# diapers.net
KiCad netlist of a schematic drawn in Altium Designer
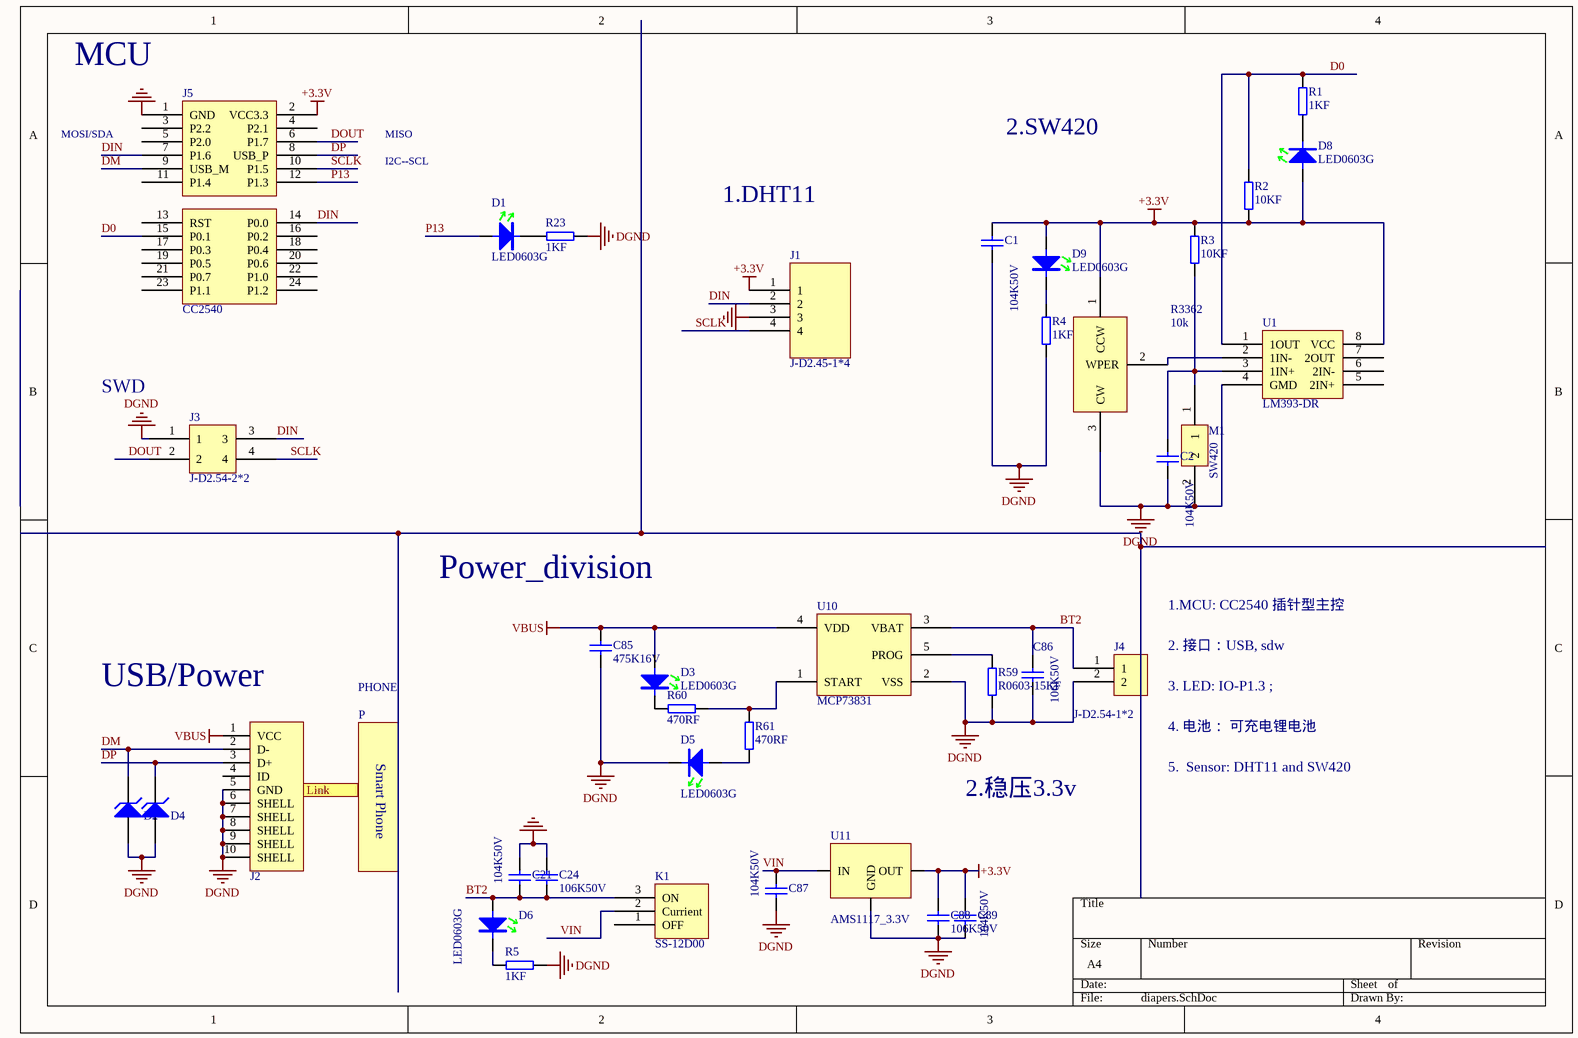
[diagram p0: diapers.SchDoc]

(export (version "E")
  (design (tool "Eeschema 10.0.6"))
  (components
    (comp (ref "C1")
      (value "104K50V")
      (footprint "C0603")
      (description "贴片电容-陶瓷")
      (libsource (lib "Capacitor") (part "C0603X7R-104K50V"))
    )
    (comp (ref "C2")
      (value "104K50V")
      (footprint "C0603")
      (description "贴片电容-陶瓷")
      (libsource (lib "Capacitor") (part "C0603X7R-104K50V"))
    )
    (comp (ref "C21")
      (value "104K50V")
      (footprint "C0603")
      (description "贴片电容-陶瓷")
      (libsource (lib "Capacitor") (part "C0603X7R-104K50V"))
    )
    (comp (ref "C24")
      (value "106K50V")
      (footprint "C0603")
      (description "贴片电容-陶瓷")
      (libsource (lib "Capacitor") (part "C0603X7R-106K50V"))
    )
    (comp (ref "C85")
      (value "475K16V")
      (footprint "C0603")
      (description "贴片电容-陶瓷")
      (libsource (lib "Capacitor") (part "C0603X7R-475K16V"))
    )
    (comp (ref "C86")
      (value "106K50V")
      (footprint "C0603")
      (description "贴片电容-陶瓷")
      (libsource (lib "Capacitor") (part "C0603X7R-106K50V"))
    )
    (comp (ref "C87")
      (value "104K50V")
      (footprint "C0603")
      (description "贴片电容-陶瓷")
      (libsource (lib "Capacitor") (part "C0603X7R-104K50V"))
    )
    (comp (ref "C88")
      (value "106K50V")
      (footprint "C0603")
      (description "贴片电容-陶瓷")
      (libsource (lib "Capacitor") (part "C0603X7R-106K50V"))
    )
    (comp (ref "C89")
      (value "104K50V")
      (footprint "C0603")
      (description "贴片电容-陶瓷")
      (libsource (lib "Capacitor") (part "C0603X7R-104K50V"))
    )
    (comp (ref "D1")
      (value "LED0603G")
      (footprint "D-LED0603G")
      (description "贴片二极管-LED")
      (libsource (lib "aiwacV2.0") (part "DLED-0603-G"))
    )
    (comp (ref "D2")
      (value "ESDA_TR1/0603")
      (footprint "HS_0603D")
      (description "Zener Diode")
      (fields (field (name "PUBLISHER") "*"))
      (libsource (lib "aiwacV2.0") (part "D Zener"))
    )
    (comp (ref "D3")
      (value "LED0603G")
      (footprint "D-LED0603G")
      (description "贴片二极管-LED")
      (libsource (lib "Diode") (part "DLED-0603-G"))
    )
    (comp (ref "D4")
      (value "ESDA_TR1/0603")
      (footprint "HS_0603D")
      (description "Zener Diode")
      (fields (field (name "PUBLISHER") "*"))
      (libsource (lib "aiwacV2.0") (part "D Zener"))
    )
    (comp (ref "D5")
      (value "LED0603G")
      (footprint "D-LED0603G")
      (description "贴片二极管-LED")
      (libsource (lib "Diode") (part "DLED-0603-G"))
    )
    (comp (ref "D6")
      (value "LED0603G")
      (footprint "D-LED0603G")
      (description "贴片二极管-LED")
      (libsource (lib "aiwacV2.0") (part "DLED-0603-G"))
    )
    (comp (ref "D8")
      (value "LED0603G")
      (footprint "D-LED0603G")
      (description "贴片二极管-LED")
      (libsource (lib "Diode") (part "DLED-0603-G"))
    )
    (comp (ref "D9")
      (value "LED0603G")
      (footprint "D-LED0603G")
      (description "贴片二极管-LED")
      (libsource (lib "Diode") (part "DLED-0603-G"))
    )
    (comp (ref "J1")
      (value "J-D2.45-1*4")
      (footprint "D2.54-1*4P")
      (libsource (lib "Connector") (part "J-D2.54-1*4单排排母"))
    )
    (comp (ref "J2")
      (value "USB-MINI-SOCKET")
      (footprint "MICRO-USB - 5.9")
      (description "USB-A卧式插座")
      (libsource (lib "epic2") (part "J-USB-MINI-SOCKET"))
    )
    (comp (ref "J3")
      (value "J-D2.54-2*2")
      (footprint "D2.54-2*2P")
      (description "双排排针-直针")
      (libsource (lib "Connector") (part "J-D2.54-2*2双排"))
    )
    (comp (ref "J4")
      (value "J-D2.54-1*2")
      (footprint "D2.54-1*2P")
      (libsource (lib "Connector") (part "J-D2.54-1*2单排"))
    )
    (comp (ref "J5")
      (value "CC2540")
      (footprint "PCBComponent_1")
      (description "蓝牙主控模块的接口")
      (libsource (lib "Module") (part "CC2540"))
    )
    (comp (ref "K1")
      (value "SS-12D00")
      (footprint "SS-12D00")
      (libsource (lib "Key") (part "SS-12D00(1P2T) 立式 柄高5MM"))
    )
    (comp (ref "M1")
      (value "SW420")
      (footprint "SW420")
      (description "长闭震动开关")
      (libsource (lib "Module") (part "SW420"))
    )
    (comp (ref "P") (value "PHONE") (libsource (lib "epic") (part "PHONE")))
    (comp (ref "R1")
      (value "1KF")
      (footprint "R0603")
      (description "贴片电阻-通用")
      (libsource (lib "Resistor") (part "R0603-1KF"))
    )
    (comp (ref "R2")
      (value "10KF")
      (footprint "R0603")
      (description "贴片电阻-通用")
      (libsource (lib "Resistor") (part "R0603-10KF"))
    )
    (comp (ref "R3")
      (value "10KF")
      (footprint "R0603")
      (description "贴片电阻-通用")
      (libsource (lib "Resistor") (part "R0603-10KF"))
    )
    (comp (ref "R4")
      (value "1KF")
      (footprint "R0603")
      (description "贴片电阻-通用")
      (libsource (lib "Resistor") (part "R0603-1KF"))
    )
    (comp (ref "R5")
      (value "1KF")
      (footprint "R0603")
      (description "贴片电阻-通用")
      (libsource (lib "Resistor") (part "R0603-1KF"))
    )
    (comp (ref "R23")
      (value "1KF")
      (footprint "R0603")
      (description "贴片电阻-通用")
      (libsource (lib "Resistor") (part "R0603-1KF"))
    )
    (comp (ref "R59")
      (value "R0603-15KF")
      (footprint "R0603")
      (description "贴片电容-通用")
      (libsource (lib "Resistor") (part "R0603-15KF"))
    )
    (comp (ref "R60")
      (value "470RF")
      (footprint "R0603")
      (description "贴片电阻-通用")
      (libsource (lib "Resistor") (part "R0603-470RF"))
    )
    (comp (ref "R61")
      (value "470RF")
      (footprint "R0603")
      (description "贴片电阻-通用")
      (libsource (lib "Resistor") (part "R0603-470RF"))
    )
    (comp (ref "R3362")
      (value "10k")
      (footprint "R3326P")
      (description "电位器精密可调电阻")
      (libsource (lib "Resistor") (part "R3362-10K"))
    )
    (comp (ref "U1")
      (value "LM393-DR")
      (footprint "LM393")
      (description "双路比较器")
      (libsource (lib "IC") (part "LM393-DR"))
    )
    (comp (ref "U10")
      (value "MCP73831")
      (footprint "SOT23-5N")
      (description "charge IC")
      (libsource (lib "IC") (part "MCP73831"))
    )
    (comp (ref "U11")
      (value "AMS1117_3.3V")
      (footprint "SOT-223")
      (libsource (lib "IC") (part "AMS1117-3.3V"))
    )
  )
  (nets
    (net (code "1") (name "+3.3V") (class "Default")
      (node (ref "C1") (pin "1") (pinfunction "1_1") (pintype "passive"))
      (node (ref "C88") (pin "2") (pinfunction "2_2") (pintype "passive"))
      (node (ref "C89") (pin "1") (pinfunction "1_1") (pintype "passive"))
      (node (ref "D8") (pin "1") (pinfunction "1_1") (pintype "passive"))
      (node (ref "D9") (pin "1") (pinfunction "1_1") (pintype "passive"))
      (node (ref "J1") (pin "1") (pinfunction "1_1") (pintype "passive"))
      (node (ref "J5") (pin "2") (pinfunction "VCC3.3_2") (pintype "passive"))
      (node (ref "R2") (pin "1") (pinfunction "1_1") (pintype "passive"))
      (node (ref "R3") (pin "2") (pinfunction "2_2") (pintype "passive"))
      (node (ref "R3362") (pin "1") (pinfunction "CCW_1") (pintype "passive"))
      (node (ref "U1") (pin "8") (pinfunction "VCC_8") (pintype "passive"))
      (node (ref "U11") (pin "2") (pinfunction "OUT_2") (pintype "passive"))
    )
    (net (code "2") (name "/BT2") (class "Default")
      (node (ref "C21") (pin "2") (pinfunction "2_2") (pintype "passive"))
      (node (ref "C24") (pin "1") (pinfunction "1_1") (pintype "passive"))
      (node (ref "C86") (pin "1") (pinfunction "1_1") (pintype "passive"))
      (node (ref "D6") (pin "1") (pinfunction "1_1") (pintype "passive"))
      (node (ref "J4") (pin "1") (pinfunction "1_1") (pintype "passive"))
      (node (ref "K1") (pin "3") (pinfunction "ON_3") (pintype "passive"))
      (node (ref "U10") (pin "3") (pinfunction "VBAT_3") (pintype "passive"))
    )
    (net (code "3") (name "/D0") (class "Default")
      (node (ref "J5") (pin "15") (pinfunction "P0.1_15") (pintype "passive"))
      (node (ref "R1") (pin "1") (pinfunction "1_1") (pintype "passive"))
      (node (ref "R2") (pin "2") (pinfunction "2_2") (pintype "passive"))
      (node (ref "U1") (pin "1") (pinfunction "1OUT_1") (pintype "passive"))
    )
    (net (code "4") (name "/DIN") (class "Default")
      (node (ref "J1") (pin "2") (pinfunction "2_2") (pintype "passive"))
      (node (ref "J3") (pin "3") (pinfunction "3_3") (pintype "passive"))
      (node (ref "J5") (pin "14") (pinfunction "P0.0_14") (pintype "passive"))
      (node (ref "J5") (pin "7") (pinfunction "P1.6_7") (pintype "passive"))
    )
    (net (code "5") (name "/DM") (class "Default")
      (node (ref "D2") (pin "2") (pinfunction "K_2") (pintype "passive"))
      (node (ref "J2") (pin "2") (pinfunction "D-_2") (pintype "passive"))
      (node (ref "J5") (pin "9") (pinfunction "USB_M_9") (pintype "passive"))
    )
    (net (code "6") (name "/DOUT") (class "Default")
      (node (ref "J3") (pin "2") (pinfunction "2_2") (pintype "passive"))
      (node (ref "J5") (pin "6") (pinfunction "P1.7_6") (pintype "passive"))
    )
    (net (code "7") (name "/DP") (class "Default")
      (node (ref "D4") (pin "2") (pinfunction "K_2") (pintype "passive"))
      (node (ref "J2") (pin "3") (pinfunction "D+_3") (pintype "passive"))
      (node (ref "J5") (pin "8") (pinfunction "USB_P_8") (pintype "passive"))
    )
    (net (code "9") (name "/P13") (class "Default")
      (node (ref "D1") (pin "1") (pinfunction "1_1") (pintype "passive"))
      (node (ref "J5") (pin "12") (pinfunction "P1.3_12") (pintype "passive"))
    )
    (net (code "10") (name "/SCLK") (class "Default")
      (node (ref "J1") (pin "4") (pinfunction "4_4") (pintype "passive"))
      (node (ref "J3") (pin "4") (pinfunction "4_4") (pintype "passive"))
      (node (ref "J5") (pin "10") (pinfunction "P1.5_10") (pintype "passive"))
    )
    (net (code "11") (name "/VIN") (class "Default")
      (node (ref "C87") (pin "1") (pinfunction "1_1") (pintype "passive"))
      (node (ref "K1") (pin "2") (pinfunction "Currient_2") (pintype "passive"))
      (node (ref "U11") (pin "3") (pinfunction "IN_3") (pintype "passive"))
    )
    (net (code "12") (name "DGND") (class "Default")
      (node (ref "C1") (pin "2") (pinfunction "2_2") (pintype "passive"))
      (node (ref "C2") (pin "2") (pinfunction "2_2") (pintype "passive"))
      (node (ref "C21") (pin "1") (pinfunction "1_1") (pintype "passive"))
      (node (ref "C24") (pin "2") (pinfunction "2_2") (pintype "passive"))
      (node (ref "C85") (pin "2") (pinfunction "2_2") (pintype "passive"))
      (node (ref "C86") (pin "2") (pinfunction "2_2") (pintype "passive"))
      (node (ref "C87") (pin "2") (pinfunction "2_2") (pintype "passive"))
      (node (ref "C88") (pin "1") (pinfunction "1_1") (pintype "passive"))
      (node (ref "C89") (pin "2") (pinfunction "2_2") (pintype "passive"))
      (node (ref "D2") (pin "1") (pinfunction "A_1") (pintype "passive"))
      (node (ref "D4") (pin "1") (pinfunction "A_1") (pintype "passive"))
      (node (ref "D5") (pin "2") (pinfunction "2_2") (pintype "passive"))
      (node (ref "J1") (pin "3") (pinfunction "3_3") (pintype "passive"))
      (node (ref "J2") (pin "10") (pinfunction "SHELL_10") (pintype "passive"))
      (node (ref "J2") (pin "5") (pinfunction "GND_5") (pintype "passive"))
      (node (ref "J2") (pin "6") (pinfunction "SHELL_6") (pintype "passive"))
      (node (ref "J2") (pin "7") (pinfunction "SHELL_7") (pintype "passive"))
      (node (ref "J2") (pin "8") (pinfunction "SHELL_8") (pintype "passive"))
      (node (ref "J2") (pin "9") (pinfunction "SHELL_9") (pintype "passive"))
      (node (ref "J3") (pin "1") (pinfunction "1_1") (pintype "passive"))
      (node (ref "J4") (pin "2") (pinfunction "2_2") (pintype "passive"))
      (node (ref "J5") (pin "1") (pinfunction "GND_1") (pintype "passive"))
      (node (ref "M1") (pin "2") (pinfunction "2_2") (pintype "passive"))
      (node (ref "R23") (pin "2") (pinfunction "2_2") (pintype "passive"))
      (node (ref "R3362") (pin "3") (pinfunction "CW_3") (pintype "passive"))
      (node (ref "R4") (pin "1") (pinfunction "1_1") (pintype "passive"))
      (node (ref "R5") (pin "2") (pinfunction "2_2") (pintype "passive"))
      (node (ref "R59") (pin "1") (pinfunction "1_1") (pintype "passive"))
      (node (ref "U1") (pin "4") (pinfunction "GMD_4") (pintype "passive"))
      (node (ref "U10") (pin "2") (pinfunction "VSS_2") (pintype "passive"))
      (node (ref "U11") (pin "1") (pinfunction "GND_1") (pintype "passive"))
    )
    (net (code "13") (name "Net-(D1-Pad2)") (class "Default")
      (node (ref "D1") (pin "2") (pinfunction "2_2") (pintype "passive"))
      (node (ref "R23") (pin "1") (pinfunction "1_1") (pintype "passive"))
    )
    (net (code "14") (name "Net-(D3-Pad2)") (class "Default")
      (node (ref "D3") (pin "2") (pinfunction "2_2") (pintype "passive"))
      (node (ref "R60") (pin "1") (pinfunction "1_1") (pintype "passive"))
    )
    (net (code "15") (name "Net-(D5-Pad1)") (class "Default")
      (node (ref "D5") (pin "1") (pinfunction "1_1") (pintype "passive"))
      (node (ref "R61") (pin "1") (pinfunction "1_1") (pintype "passive"))
    )
    (net (code "16") (name "Net-(D6-Pad2)") (class "Default")
      (node (ref "D6") (pin "2") (pinfunction "2_2") (pintype "passive"))
      (node (ref "R5") (pin "1") (pinfunction "1_1") (pintype "passive"))
    )
    (net (code "17") (name "Net-(D8-Pad2)") (class "Default")
      (node (ref "D8") (pin "2") (pinfunction "2_2") (pintype "passive"))
      (node (ref "R1") (pin "2") (pinfunction "2_2") (pintype "passive"))
    )
    (net (code "18") (name "Net-(D9-Pad2)") (class "Default")
      (node (ref "D9") (pin "2") (pinfunction "2_2") (pintype "passive"))
      (node (ref "R4") (pin "2") (pinfunction "2_2") (pintype "passive"))
    )
    (net (code "19") (name "Net-(R3362-WPER)") (class "Default")
      (node (ref "R3362") (pin "2") (pinfunction "WPER_2") (pintype "passive"))
      (node (ref "U1") (pin "2") (pinfunction "1IN-_2") (pintype "passive"))
    )
    (net (code "20") (name "Net-(U1-1IN+)") (class "Default")
      (node (ref "C2") (pin "1") (pinfunction "1_1") (pintype "passive"))
      (node (ref "M1") (pin "1") (pinfunction "1_1") (pintype "passive"))
      (node (ref "R3") (pin "1") (pinfunction "1_1") (pintype "passive"))
      (node (ref "U1") (pin "3") (pinfunction "1IN+_3") (pintype "passive"))
    )
    (net (code "21") (name "Net-(U10-PROG)") (class "Default")
      (node (ref "R59") (pin "2") (pinfunction "2_2") (pintype "passive"))
      (node (ref "U10") (pin "5") (pinfunction "PROG_5") (pintype "passive"))
    )
    (net (code "22") (name "Net-(U10-START)") (class "Default")
      (node (ref "R60") (pin "2") (pinfunction "2_2") (pintype "passive"))
      (node (ref "R61") (pin "2") (pinfunction "2_2") (pintype "passive"))
      (node (ref "U10") (pin "1") (pinfunction "START_1") (pintype "passive"))
    )
    (net (code "23") (name "VBUS") (class "Default")
      (node (ref "C85") (pin "1") (pinfunction "1_1") (pintype "passive"))
      (node (ref "D3") (pin "1") (pinfunction "1_1") (pintype "passive"))
      (node (ref "J2") (pin "1") (pinfunction "VCC_1") (pintype "passive"))
      (node (ref "U10") (pin "4") (pinfunction "VDD_4") (pintype "passive"))
    )
    (net (code "24") (name "unconnected-(J2-ID-Pad4)") (class "Default")
      (node (ref "J2") (pin "4") (pinfunction "ID_4") (pintype "passive"))
    )
    (net (code "25") (name "unconnected-(J5-P0.2-Pad16)") (class "Default")
      (node (ref "J5") (pin "16") (pinfunction "P0.2_16") (pintype "passive"))
    )
    (net (code "26") (name "unconnected-(J5-P0.3-Pad17)") (class "Default")
      (node (ref "J5") (pin "17") (pinfunction "P0.3_17") (pintype "passive"))
    )
    (net (code "27") (name "unconnected-(J5-P0.4-Pad18)") (class "Default")
      (node (ref "J5") (pin "18") (pinfunction "P0.4_18") (pintype "passive"))
    )
    (net (code "28") (name "unconnected-(J5-P0.5-Pad19)") (class "Default")
      (node (ref "J5") (pin "19") (pinfunction "P0.5_19") (pintype "passive"))
    )
    (net (code "29") (name "unconnected-(J5-P0.6-Pad20)") (class "Default")
      (node (ref "J5") (pin "20") (pinfunction "P0.6_20") (pintype "passive"))
    )
    (net (code "30") (name "unconnected-(J5-P0.7-Pad21)") (class "Default")
      (node (ref "J5") (pin "21") (pinfunction "P0.7_21") (pintype "passive"))
    )
    (net (code "31") (name "unconnected-(J5-P1.0-Pad22)") (class "Default")
      (node (ref "J5") (pin "22") (pinfunction "P1.0_22") (pintype "passive"))
    )
    (net (code "32") (name "unconnected-(J5-P1.1-Pad23)") (class "Default")
      (node (ref "J5") (pin "23") (pinfunction "P1.1_23") (pintype "passive"))
    )
    (net (code "33") (name "unconnected-(J5-P1.2-Pad24)") (class "Default")
      (node (ref "J5") (pin "24") (pinfunction "P1.2_24") (pintype "passive"))
    )
    (net (code "34") (name "unconnected-(J5-P1.4-Pad11)") (class "Default")
      (node (ref "J5") (pin "11") (pinfunction "P1.4_11") (pintype "passive"))
    )
    (net (code "35") (name "unconnected-(J5-P2.0-Pad5)") (class "Default")
      (node (ref "J5") (pin "5") (pinfunction "P2.0_5") (pintype "passive"))
    )
    (net (code "36") (name "unconnected-(J5-P2.1-Pad4)") (class "Default")
      (node (ref "J5") (pin "4") (pinfunction "P2.1_4") (pintype "passive"))
    )
    (net (code "37") (name "unconnected-(J5-P2.2-Pad3)") (class "Default")
      (node (ref "J5") (pin "3") (pinfunction "P2.2_3") (pintype "passive"))
    )
    (net (code "38") (name "unconnected-(J5-RST-Pad13)") (class "Default")
      (node (ref "J5") (pin "13") (pinfunction "RST_13") (pintype "passive"))
    )
    (net (code "39") (name "unconnected-(K1-OFF-Pad1)") (class "Default")
      (node (ref "K1") (pin "1") (pinfunction "OFF_1") (pintype "passive"))
    )
    (net (code "40") (name "unconnected-(U1-2IN+-Pad5)") (class "Default")
      (node (ref "U1") (pin "5") (pinfunction "2IN+_5") (pintype "passive"))
    )
    (net (code "41") (name "unconnected-(U1-2IN--Pad6)") (class "Default")
      (node (ref "U1") (pin "6") (pinfunction "2IN-_6") (pintype "passive"))
    )
    (net (code "42") (name "unconnected-(U1-2OUT-Pad7)") (class "Default")
      (node (ref "U1") (pin "7") (pinfunction "2OUT_7") (pintype "passive"))
    )
  )
)
